# Due_Breakout_Board_supporting_circuits.net
KiCad netlist of a schematic drawn in Altium Designer
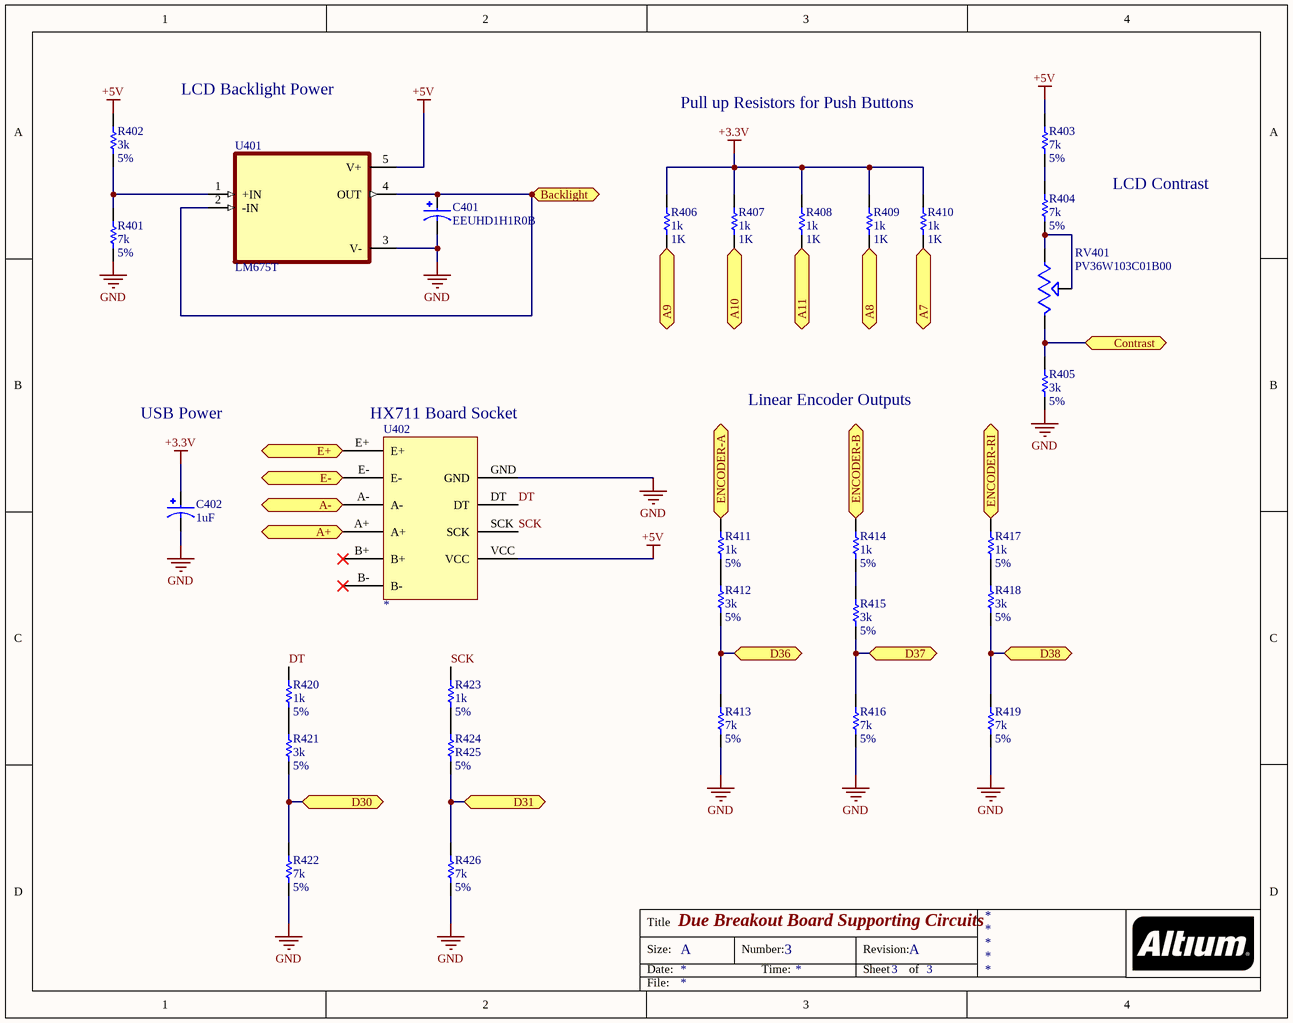
[diagram p0: Due_Breakout_Board supporting circuits.SchDoc]

(export (version "E")
  (design (tool "Eeschema 10.0.6"))
  (components
    (comp (ref "C401")
      (value "EEUHD1H1R0B")
      (footprint "CAPPRD500W50D500H1100")
      (description "Cap Aluminum Lytic 1uF 50V 20% (5 X 11mm) Radial 5mm 10mA 1000h 105Â°C Automotive Ammo")
      (fields (field (name "MF") "Panasonic"))
      (libsource (lib "EEUHD1H1R0B") (part "EEUHD1H1R0B"))
    )
    (comp (ref "C402")
      (value "1uF")
      (footprint "CAPPRD500W50D500H1100")
      (description "Cap Aluminum Lytic 1uF 50V 20% (5 X 11mm) Radial 5mm 10mA 1000h 105Â°C Automotive Ammo")
      (fields (field (name "MF") "Panasonic") (field (name "MP") "EEUHD1H1R0B"))
      (libsource (lib "EEUHD1H1R0B") (part "EEUHD1H1R0B"))
    )
    (comp (ref "R401")
      (value "7k")
      (footprint "AXIAL-0.3")
      (description "Resistor")
      (fields (field (name "ALTIUM_VALUE") "5%") (field (name "PUBLISHER") "Altium Limited"))
      (libsource (lib "Miscellaneous Devices") (part "Res1"))
    )
    (comp (ref "R402")
      (value "3k")
      (footprint "AXIAL-0.3")
      (description "Resistor")
      (fields (field (name "ALTIUM_VALUE") "5%") (field (name "PUBLISHER") "Altium Limited"))
      (libsource (lib "Miscellaneous Devices") (part "Res1"))
    )
    (comp (ref "R403")
      (value "7k")
      (footprint "AXIAL-0.3")
      (description "Resistor")
      (fields (field (name "ALTIUM_VALUE") "5%") (field (name "PUBLISHER") "Altium Limited"))
      (libsource (lib "Miscellaneous Devices") (part "Res1"))
    )
    (comp (ref "R404")
      (value "7k")
      (footprint "AXIAL-0.3")
      (description "Resistor")
      (fields (field (name "ALTIUM_VALUE") "5%") (field (name "PUBLISHER") "Altium Limited"))
      (libsource (lib "Miscellaneous Devices") (part "Res1"))
    )
    (comp (ref "R405")
      (value "3k")
      (footprint "AXIAL-0.3")
      (description "Resistor")
      (fields (field (name "ALTIUM_VALUE") "5%") (field (name "PUBLISHER") "Altium Limited"))
      (libsource (lib "Miscellaneous Devices") (part "Res1"))
    )
    (comp (ref "R406")
      (value "1k")
      (footprint "AXIAL-0.3")
      (description "Resistor")
      (fields (field (name "ALTIUM_VALUE") "1K") (field (name "PUBLISHER") "Altium Limited"))
      (libsource (lib "Miscellaneous Devices") (part "Res1"))
    )
    (comp (ref "R407")
      (value "1k")
      (footprint "AXIAL-0.3")
      (description "Resistor")
      (fields (field (name "ALTIUM_VALUE") "1K") (field (name "PUBLISHER") "Altium Limited"))
      (libsource (lib "Miscellaneous Devices") (part "Res1"))
    )
    (comp (ref "R408")
      (value "1k")
      (footprint "AXIAL-0.3")
      (description "Resistor")
      (fields (field (name "ALTIUM_VALUE") "1K") (field (name "PUBLISHER") "Altium Limited"))
      (libsource (lib "Miscellaneous Devices") (part "Res1"))
    )
    (comp (ref "R409")
      (value "1k")
      (footprint "AXIAL-0.3")
      (description "Resistor")
      (fields (field (name "ALTIUM_VALUE") "1K") (field (name "PUBLISHER") "Altium Limited"))
      (libsource (lib "Miscellaneous Devices") (part "Res1"))
    )
    (comp (ref "R410")
      (value "1k")
      (footprint "AXIAL-0.3")
      (description "Resistor")
      (fields (field (name "ALTIUM_VALUE") "1K") (field (name "PUBLISHER") "Altium Limited"))
      (libsource (lib "Miscellaneous Devices") (part "Res1"))
    )
    (comp (ref "R411")
      (value "1k")
      (footprint "AXIAL-0.3")
      (description "Resistor")
      (fields (field (name "ALTIUM_VALUE") "5%") (field (name "PUBLISHER") "Altium Limited"))
      (libsource (lib "Miscellaneous Devices") (part "Res1"))
    )
    (comp (ref "R412")
      (value "3k")
      (footprint "AXIAL-0.3")
      (description "Resistor")
      (fields (field (name "ALTIUM_VALUE") "5%") (field (name "PUBLISHER") "Altium Limited"))
      (libsource (lib "Miscellaneous Devices") (part "Res1"))
    )
    (comp (ref "R413")
      (value "7k")
      (footprint "AXIAL-0.3")
      (description "Resistor")
      (fields (field (name "ALTIUM_VALUE") "5%") (field (name "PUBLISHER") "Altium Limited"))
      (libsource (lib "Miscellaneous Devices") (part "Res1"))
    )
    (comp (ref "R414")
      (value "1k")
      (footprint "AXIAL-0.3")
      (description "Resistor")
      (fields (field (name "ALTIUM_VALUE") "5%") (field (name "PUBLISHER") "Altium Limited"))
      (libsource (lib "Miscellaneous Devices") (part "Res1"))
    )
    (comp (ref "R415")
      (value "3k")
      (footprint "AXIAL-0.3")
      (description "Resistor")
      (fields (field (name "ALTIUM_VALUE") "5%") (field (name "PUBLISHER") "Altium Limited"))
      (libsource (lib "Miscellaneous Devices") (part "Res1"))
    )
    (comp (ref "R416")
      (value "7k")
      (footprint "AXIAL-0.3")
      (description "Resistor")
      (fields (field (name "ALTIUM_VALUE") "5%") (field (name "PUBLISHER") "Altium Limited"))
      (libsource (lib "Miscellaneous Devices") (part "Res1"))
    )
    (comp (ref "R417")
      (value "1k")
      (footprint "AXIAL-0.3")
      (description "Resistor")
      (fields (field (name "ALTIUM_VALUE") "5%") (field (name "PUBLISHER") "Altium Limited"))
      (libsource (lib "Miscellaneous Devices") (part "Res1"))
    )
    (comp (ref "R418")
      (value "3k")
      (footprint "AXIAL-0.3")
      (description "Resistor")
      (fields (field (name "ALTIUM_VALUE") "5%") (field (name "PUBLISHER") "Altium Limited"))
      (libsource (lib "Miscellaneous Devices") (part "Res1"))
    )
    (comp (ref "R419")
      (value "7k")
      (footprint "AXIAL-0.3")
      (description "Resistor")
      (fields (field (name "ALTIUM_VALUE") "5%") (field (name "PUBLISHER") "Altium Limited"))
      (libsource (lib "Miscellaneous Devices") (part "Res1"))
    )
    (comp (ref "R420")
      (value "1k")
      (footprint "AXIAL-0.3")
      (description "Resistor")
      (fields (field (name "ALTIUM_VALUE") "5%") (field (name "PUBLISHER") "Altium Limited"))
      (libsource (lib "Miscellaneous Devices") (part "Res1"))
    )
    (comp (ref "R421")
      (value "3k")
      (footprint "AXIAL-0.3")
      (description "Resistor")
      (fields (field (name "ALTIUM_VALUE") "5%") (field (name "PUBLISHER") "Altium Limited"))
      (libsource (lib "Miscellaneous Devices") (part "Res1"))
    )
    (comp (ref "R422")
      (value "7k")
      (footprint "AXIAL-0.3")
      (description "Resistor")
      (fields (field (name "ALTIUM_VALUE") "5%") (field (name "PUBLISHER") "Altium Limited"))
      (libsource (lib "Miscellaneous Devices") (part "Res1"))
    )
    (comp (ref "R423")
      (value "1k")
      (footprint "AXIAL-0.3")
      (description "Resistor")
      (fields (field (name "ALTIUM_VALUE") "5%") (field (name "PUBLISHER") "Altium Limited"))
      (libsource (lib "Miscellaneous Devices") (part "Res1"))
    )
    (comp (ref "R424")
      (value "R425")
      (footprint "AXIAL-0.3")
      (description "Resistor")
      (fields (field (name "ALTIUM_VALUE") "5%") (field (name "PUBLISHER") "Altium Limited"))
      (libsource (lib "Miscellaneous Devices") (part "Res1"))
    )
    (comp (ref "R426")
      (value "7k")
      (footprint "AXIAL-0.3")
      (description "Resistor")
      (fields (field (name "ALTIUM_VALUE") "5%") (field (name "PUBLISHER") "Altium Limited"))
      (libsource (lib "Miscellaneous Devices") (part "Res1"))
    )
    (comp (ref "RV401")
      (value "PV36W103C01B00")
      (footprint "TRIM_PV36W103C01B00")
      (description "10 kOhms 0.5W, 1/2W PC Pins Through Hole Trimmer Potentiometer Cermet 25 Turn Top Adjustment")
      (fields (field (name "MF") "Bourns"))
      (libsource (lib "PV36W103C01B00") (part "PV36W103C01B00"))
    )
    (comp (ref "U401")
      (value "LM675T")
      (footprint "TO170P1016X470X2092-5")
      (description "Power Operational Amplifier 5-TO-220 0 to 70")
      (fields (field (name "MF") "Texas Instruments"))
      (libsource (lib "LM675T") (part "LM675T"))
    )
    (comp (ref "U402") (value "*") (footprint "HX711_MOD") (libsource (lib "Components") (part "HX711_MOD")))
  )
  (nets
    (net (code "1") (name "+3.3V") (class "Default")
      (node (ref "C402") (pin "P") (pinfunction "P_P") (pintype "passive"))
      (node (ref "R406") (pin "2") (pinfunction "2_2") (pintype "passive"))
      (node (ref "R407") (pin "2") (pinfunction "2_2") (pintype "passive"))
      (node (ref "R408") (pin "2") (pinfunction "2_2") (pintype "passive"))
      (node (ref "R409") (pin "1") (pinfunction "1_1") (pintype "passive"))
      (node (ref "R410") (pin "1") (pinfunction "1_1") (pintype "passive"))
    )
    (net (code "2") (name "+5V") (class "Default")
      (node (ref "R402") (pin "2") (pinfunction "2_2") (pintype "passive"))
      (node (ref "R403") (pin "2") (pinfunction "2_2") (pintype "passive"))
      (node (ref "U401") (pin "5") (pinfunction "V+_5") (pintype "power_in"))
      (node (ref "U402") (pin "VCC") (pinfunction "VCC_VCC") (pintype "passive"))
    )
    (net (code "3") (name "/A+") (class "Default")
      (node (ref "U402") (pin "A+") (pinfunction "A+_A+") (pintype "passive"))
    )
    (net (code "4") (name "/A-") (class "Default")
      (node (ref "U402") (pin "A-") (pinfunction "A-_A-") (pintype "passive"))
    )
    (net (code "5") (name "/A7") (class "Default")
      (node (ref "R410") (pin "2") (pinfunction "2_2") (pintype "passive"))
    )
    (net (code "6") (name "/A8") (class "Default")
      (node (ref "R409") (pin "2") (pinfunction "2_2") (pintype "passive"))
    )
    (net (code "7") (name "/A9") (class "Default")
      (node (ref "R406") (pin "1") (pinfunction "1_1") (pintype "passive"))
    )
    (net (code "8") (name "/A10") (class "Default")
      (node (ref "R407") (pin "1") (pinfunction "1_1") (pintype "passive"))
    )
    (net (code "9") (name "/A11") (class "Default")
      (node (ref "R408") (pin "1") (pinfunction "1_1") (pintype "passive"))
    )
    (net (code "10") (name "/Backlight") (class "Default")
      (node (ref "C401") (pin "P") (pinfunction "P_P") (pintype "passive"))
      (node (ref "U401") (pin "2") (pinfunction "-IN_2") (pintype "input"))
      (node (ref "U401") (pin "4") (pinfunction "OUT_4") (pintype "output"))
    )
    (net (code "11") (name "/Contrast") (class "Default")
      (node (ref "R405") (pin "2") (pinfunction "2_2") (pintype "passive"))
      (node (ref "RV401") (pin "3") (pinfunction "3_3") (pintype "passive"))
    )
    (net (code "12") (name "/D30") (class "Default")
      (node (ref "R421") (pin "1") (pinfunction "1_1") (pintype "passive"))
      (node (ref "R422") (pin "2") (pinfunction "2_2") (pintype "passive"))
    )
    (net (code "13") (name "/D31") (class "Default")
      (node (ref "R424") (pin "1") (pinfunction "1_1") (pintype "passive"))
      (node (ref "R426") (pin "2") (pinfunction "2_2") (pintype "passive"))
    )
    (net (code "14") (name "/D36") (class "Default")
      (node (ref "R412") (pin "1") (pinfunction "1_1") (pintype "passive"))
      (node (ref "R413") (pin "2") (pinfunction "2_2") (pintype "passive"))
    )
    (net (code "15") (name "/D37") (class "Default")
      (node (ref "R415") (pin "1") (pinfunction "1_1") (pintype "passive"))
      (node (ref "R416") (pin "2") (pinfunction "2_2") (pintype "passive"))
    )
    (net (code "16") (name "/D38") (class "Default")
      (node (ref "R418") (pin "1") (pinfunction "1_1") (pintype "passive"))
      (node (ref "R419") (pin "2") (pinfunction "2_2") (pintype "passive"))
    )
    (net (code "17") (name "/DT") (class "Default")
      (node (ref "R420") (pin "2") (pinfunction "2_2") (pintype "passive"))
      (node (ref "U402") (pin "DT") (pinfunction "DT_DT") (pintype "passive"))
    )
    (net (code "18") (name "/E+") (class "Default")
      (node (ref "U402") (pin "E+") (pinfunction "E+_E+") (pintype "passive"))
    )
    (net (code "19") (name "/E-") (class "Default")
      (node (ref "U402") (pin "E-") (pinfunction "E-_E-") (pintype "passive"))
    )
    (net (code "20") (name "/ENCODER-A") (class "Default")
      (node (ref "R411") (pin "2") (pinfunction "2_2") (pintype "passive"))
    )
    (net (code "21") (name "/ENCODER-B") (class "Default")
      (node (ref "R414") (pin "2") (pinfunction "2_2") (pintype "passive"))
    )
    (net (code "22") (name "/ENCODER-RI") (class "Default")
      (node (ref "R417") (pin "2") (pinfunction "2_2") (pintype "passive"))
    )
    (net (code "23") (name "/SCK") (class "Default")
      (node (ref "R423") (pin "2") (pinfunction "2_2") (pintype "passive"))
      (node (ref "U402") (pin "SCK") (pinfunction "SCK_SCK") (pintype "passive"))
    )
    (net (code "24") (name "GND") (class "Default")
      (node (ref "C401") (pin "N") (pinfunction "N_N") (pintype "passive"))
      (node (ref "C402") (pin "N") (pinfunction "N_N") (pintype "passive"))
      (node (ref "R401") (pin "1") (pinfunction "1_1") (pintype "passive"))
      (node (ref "R405") (pin "1") (pinfunction "1_1") (pintype "passive"))
      (node (ref "R413") (pin "1") (pinfunction "1_1") (pintype "passive"))
      (node (ref "R416") (pin "1") (pinfunction "1_1") (pintype "passive"))
      (node (ref "R419") (pin "1") (pinfunction "1_1") (pintype "passive"))
      (node (ref "R422") (pin "1") (pinfunction "1_1") (pintype "passive"))
      (node (ref "R426") (pin "1") (pinfunction "1_1") (pintype "passive"))
      (node (ref "U401") (pin "3") (pinfunction "V-_3") (pintype "power_in"))
      (node (ref "U402") (pin "GND") (pinfunction "GND_GND") (pintype "passive"))
    )
    (net (code "25") (name "Net-(R403-Pad1)") (class "Default")
      (node (ref "R403") (pin "1") (pinfunction "1_1") (pintype "passive"))
      (node (ref "R404") (pin "2") (pinfunction "2_2") (pintype "passive"))
    )
    (net (code "26") (name "Net-(R404-Pad1)") (class "Default")
      (node (ref "R404") (pin "1") (pinfunction "1_1") (pintype "passive"))
      (node (ref "RV401") (pin "1") (pinfunction "1_1") (pintype "passive"))
      (node (ref "RV401") (pin "2") (pinfunction "2_2") (pintype "passive"))
    )
    (net (code "27") (name "Net-(R411-Pad1)") (class "Default")
      (node (ref "R411") (pin "1") (pinfunction "1_1") (pintype "passive"))
      (node (ref "R412") (pin "2") (pinfunction "2_2") (pintype "passive"))
    )
    (net (code "28") (name "Net-(R414-Pad1)") (class "Default")
      (node (ref "R414") (pin "1") (pinfunction "1_1") (pintype "passive"))
      (node (ref "R415") (pin "2") (pinfunction "2_2") (pintype "passive"))
    )
    (net (code "29") (name "Net-(R417-Pad1)") (class "Default")
      (node (ref "R417") (pin "1") (pinfunction "1_1") (pintype "passive"))
      (node (ref "R418") (pin "2") (pinfunction "2_2") (pintype "passive"))
    )
    (net (code "30") (name "Net-(R420-Pad1)") (class "Default")
      (node (ref "R420") (pin "1") (pinfunction "1_1") (pintype "passive"))
      (node (ref "R421") (pin "2") (pinfunction "2_2") (pintype "passive"))
    )
    (net (code "31") (name "Net-(R423-Pad1)") (class "Default")
      (node (ref "R423") (pin "1") (pinfunction "1_1") (pintype "passive"))
      (node (ref "R424") (pin "2") (pinfunction "2_2") (pintype "passive"))
    )
    (net (code "32") (name "Net-(U401-+IN)") (class "Default")
      (node (ref "R401") (pin "2") (pinfunction "2_2") (pintype "passive"))
      (node (ref "R402") (pin "1") (pinfunction "1_1") (pintype "passive"))
      (node (ref "U401") (pin "1") (pinfunction "+IN_1") (pintype "input"))
    )
    (net (code "33") (name "unconnected-(U402-PadB+)") (class "Default")
      (node (ref "U402") (pin "B+") (pinfunction "B+_B+") (pintype "passive+no_connect"))
    )
    (net (code "34") (name "unconnected-(U402-PadB-)") (class "Default")
      (node (ref "U402") (pin "B-") (pinfunction "B-_B-") (pintype "passive+no_connect"))
    )
  )
)
